# Connection.net
KiCad netlist of a schematic drawn in Altium Designer
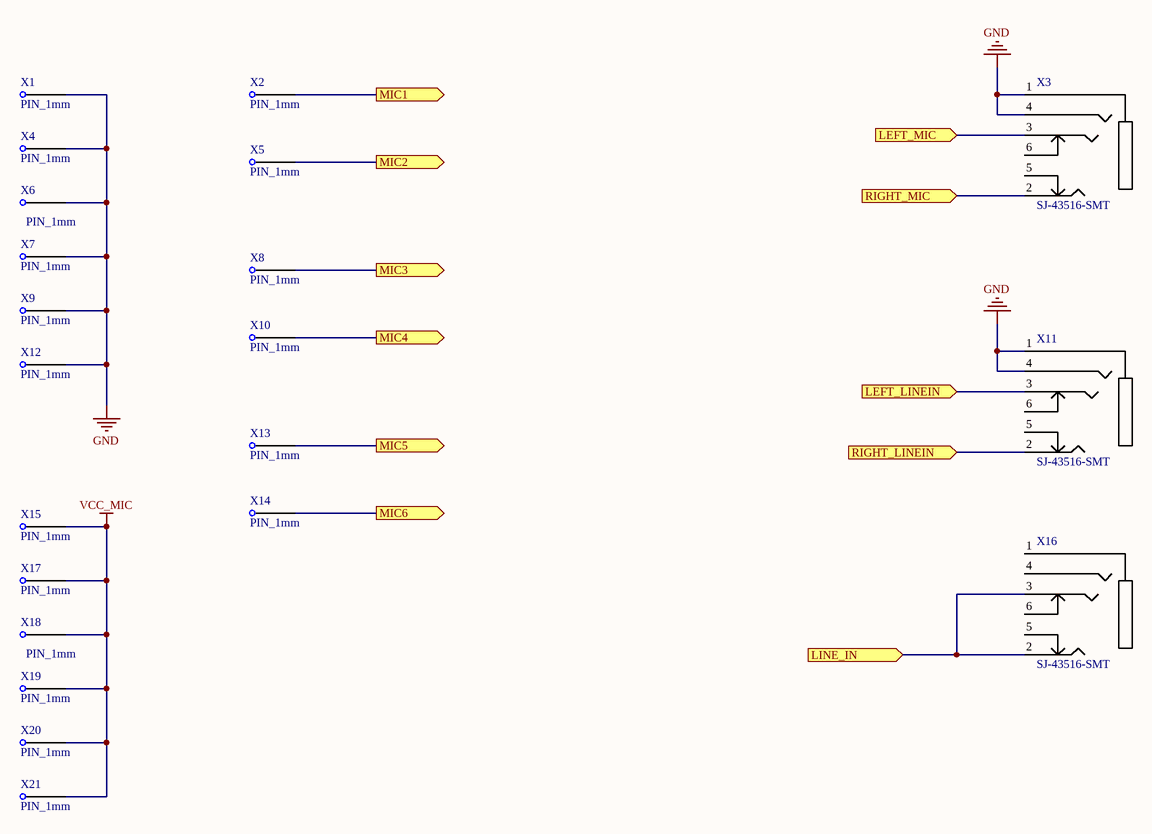
[diagram p0: Connection.SchDoc]

(export (version "E")
  (design (tool "Eeschema 10.0.6"))
  (components
    (comp (ref "X1")
      (value "PIN_1mm")
      (footprint "PIN_1mm")
      (libsource (lib "gprs_modem_2") (part "PIN_1mm"))
    )
    (comp (ref "X2")
      (value "PIN_1mm")
      (footprint "PIN_1mm")
      (libsource (lib "gprs_modem_2") (part "PIN_1mm"))
    )
    (comp (ref "X3")
      (value "SJ-43516-SMT")
      (footprint "SJ-43516-SMT")
      (description "3.5mm connector 4 conductors")
      (libsource (lib "gprs_modem_2") (part "SJ-43516-SMT"))
    )
    (comp (ref "X4")
      (value "PIN_1mm")
      (footprint "PIN_1mm")
      (libsource (lib "gprs_modem_2") (part "PIN_1mm"))
    )
    (comp (ref "X5")
      (value "PIN_1mm")
      (footprint "PIN_1mm")
      (libsource (lib "gprs_modem_2") (part "PIN_1mm"))
    )
    (comp (ref "X6")
      (value "PIN_1mm")
      (footprint "PIN_1mm")
      (libsource (lib "gprs_modem_2") (part "PIN_1mm"))
    )
    (comp (ref "X7")
      (value "PIN_1mm")
      (footprint "PIN_1mm")
      (libsource (lib "gprs_modem_2") (part "PIN_1mm"))
    )
    (comp (ref "X8")
      (value "PIN_1mm")
      (footprint "PIN_1mm")
      (libsource (lib "gprs_modem_2") (part "PIN_1mm"))
    )
    (comp (ref "X9")
      (value "PIN_1mm")
      (footprint "PIN_1mm")
      (libsource (lib "gprs_modem_2") (part "PIN_1mm"))
    )
    (comp (ref "X10")
      (value "PIN_1mm")
      (footprint "PIN_1mm")
      (libsource (lib "gprs_modem_2") (part "PIN_1mm"))
    )
    (comp (ref "X11")
      (value "SJ-43516-SMT")
      (footprint "SJ-43516-SMT")
      (description "3.5mm connector 4 conductors")
      (libsource (lib "gprs_modem_2") (part "SJ-43516-SMT"))
    )
    (comp (ref "X12")
      (value "PIN_1mm")
      (footprint "PIN_1mm")
      (libsource (lib "gprs_modem_2") (part "PIN_1mm"))
    )
    (comp (ref "X13")
      (value "PIN_1mm")
      (footprint "PIN_1mm")
      (libsource (lib "gprs_modem_2") (part "PIN_1mm"))
    )
    (comp (ref "X14")
      (value "PIN_1mm")
      (footprint "PIN_1mm")
      (libsource (lib "gprs_modem_2") (part "PIN_1mm"))
    )
    (comp (ref "X15")
      (value "PIN_1mm")
      (footprint "PIN_1mm")
      (libsource (lib "gprs_modem_2") (part "PIN_1mm"))
    )
    (comp (ref "X16")
      (value "SJ-43516-SMT")
      (footprint "SJ-43516-SMT")
      (description "3.5mm connector 4 conductors")
      (libsource (lib "gprs_modem_2") (part "SJ-43516-SMT"))
    )
    (comp (ref "X17")
      (value "PIN_1mm")
      (footprint "PIN_1mm")
      (libsource (lib "gprs_modem_2") (part "PIN_1mm"))
    )
    (comp (ref "X18")
      (value "PIN_1mm")
      (footprint "PIN_1mm")
      (libsource (lib "gprs_modem_2") (part "PIN_1mm"))
    )
    (comp (ref "X19")
      (value "PIN_1mm")
      (footprint "PIN_1mm")
      (libsource (lib "gprs_modem_2") (part "PIN_1mm"))
    )
    (comp (ref "X20")
      (value "PIN_1mm")
      (footprint "PIN_1mm")
      (libsource (lib "gprs_modem_2") (part "PIN_1mm"))
    )
    (comp (ref "X21")
      (value "PIN_1mm")
      (footprint "PIN_1mm")
      (libsource (lib "gprs_modem_2") (part "PIN_1mm"))
    )
  )
  (nets
    (net (code "1") (name "/LEFT_LINEIN") (class "Default")
      (node (ref "X11") (pin "3") (pinfunction "3_3") (pintype "passive"))
    )
    (net (code "2") (name "/LEFT_MIC") (class "Default")
      (node (ref "X3") (pin "3") (pinfunction "3_3") (pintype "passive"))
    )
    (net (code "3") (name "/LINE_IN") (class "Default")
      (node (ref "X16") (pin "2") (pinfunction "2_2") (pintype "passive"))
      (node (ref "X16") (pin "3") (pinfunction "3_3") (pintype "passive"))
    )
    (net (code "4") (name "/MIC1") (class "Default")
      (node (ref "X2") (pin "1") (pinfunction "1_1") (pintype "passive"))
    )
    (net (code "5") (name "/MIC2") (class "Default")
      (node (ref "X5") (pin "1") (pinfunction "1_1") (pintype "passive"))
    )
    (net (code "6") (name "/MIC3") (class "Default")
      (node (ref "X8") (pin "1") (pinfunction "1_1") (pintype "passive"))
    )
    (net (code "7") (name "/MIC4") (class "Default")
      (node (ref "X10") (pin "1") (pinfunction "1_1") (pintype "passive"))
    )
    (net (code "8") (name "/MIC5") (class "Default")
      (node (ref "X13") (pin "1") (pinfunction "1_1") (pintype "passive"))
    )
    (net (code "9") (name "/MIC6") (class "Default")
      (node (ref "X14") (pin "1") (pinfunction "1_1") (pintype "passive"))
    )
    (net (code "10") (name "/RIGHT_LINEIN") (class "Default")
      (node (ref "X11") (pin "2") (pinfunction "2_2") (pintype "passive"))
    )
    (net (code "11") (name "/RIGHT_MIC") (class "Default")
      (node (ref "X3") (pin "2") (pinfunction "2_2") (pintype "passive"))
    )
    (net (code "12") (name "GND") (class "Default")
      (node (ref "X1") (pin "1") (pinfunction "1_1") (pintype "passive"))
      (node (ref "X11") (pin "1") (pinfunction "1_1") (pintype "passive"))
      (node (ref "X11") (pin "4") (pinfunction "4_4") (pintype "passive"))
      (node (ref "X12") (pin "1") (pinfunction "1_1") (pintype "passive"))
      (node (ref "X3") (pin "1") (pinfunction "1_1") (pintype "passive"))
      (node (ref "X3") (pin "4") (pinfunction "4_4") (pintype "passive"))
      (node (ref "X4") (pin "1") (pinfunction "1_1") (pintype "passive"))
      (node (ref "X6") (pin "1") (pinfunction "1_1") (pintype "passive"))
      (node (ref "X7") (pin "1") (pinfunction "1_1") (pintype "passive"))
      (node (ref "X9") (pin "1") (pinfunction "1_1") (pintype "passive"))
    )
    (net (code "13") (name "VCC_MIC") (class "Default")
      (node (ref "X15") (pin "1") (pinfunction "1_1") (pintype "passive"))
      (node (ref "X17") (pin "1") (pinfunction "1_1") (pintype "passive"))
      (node (ref "X18") (pin "1") (pinfunction "1_1") (pintype "passive"))
      (node (ref "X19") (pin "1") (pinfunction "1_1") (pintype "passive"))
      (node (ref "X20") (pin "1") (pinfunction "1_1") (pintype "passive"))
      (node (ref "X21") (pin "1") (pinfunction "1_1") (pintype "passive"))
    )
    (net (code "14") (name "unconnected-(X3-Pad5)") (class "Default")
      (node (ref "X3") (pin "5") (pinfunction "5_5") (pintype "passive"))
    )
    (net (code "15") (name "unconnected-(X3-Pad6)") (class "Default")
      (node (ref "X3") (pin "6") (pinfunction "6_6") (pintype "passive"))
    )
    (net (code "16") (name "unconnected-(X11-Pad5)") (class "Default")
      (node (ref "X11") (pin "5") (pinfunction "5_5") (pintype "passive"))
    )
    (net (code "17") (name "unconnected-(X11-Pad6)") (class "Default")
      (node (ref "X11") (pin "6") (pinfunction "6_6") (pintype "passive"))
    )
    (net (code "18") (name "unconnected-(X16-Pad1)") (class "Default")
      (node (ref "X16") (pin "1") (pinfunction "1_1") (pintype "passive"))
    )
    (net (code "19") (name "unconnected-(X16-Pad4)") (class "Default")
      (node (ref "X16") (pin "4") (pinfunction "4_4") (pintype "passive"))
    )
    (net (code "20") (name "unconnected-(X16-Pad5)") (class "Default")
      (node (ref "X16") (pin "5") (pinfunction "5_5") (pintype "passive"))
    )
    (net (code "21") (name "unconnected-(X16-Pad6)") (class "Default")
      (node (ref "X16") (pin "6") (pinfunction "6_6") (pintype "passive"))
    )
  )
)
